# CyloRen-v_6_0.net
KiCad netlist of a schematic drawn in EAGLE
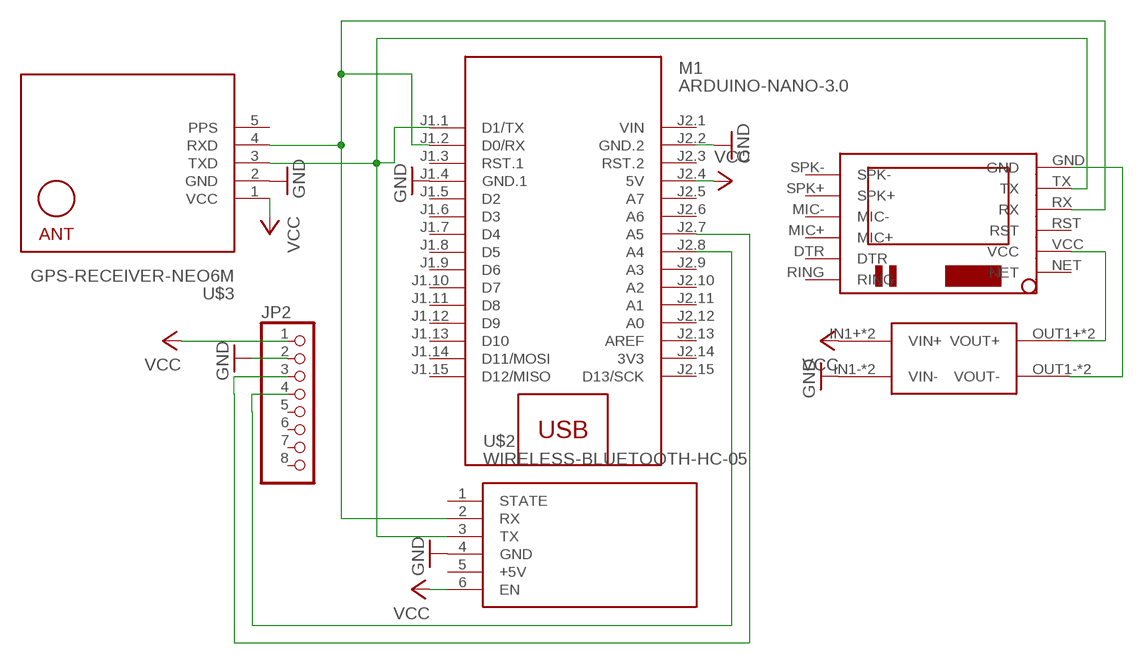
[diagram p0: schematic, sheet 1]

(export (version "E")
  (design (tool "Eeschema 10.0.6"))
  (components
    (comp (ref "JP2")
      (value "PINHD-1X8BIG")
      (footprint "eagle-import:1X08-BIG")
      (libsource (lib "eagle-import") (part "PINHD-1X8BIG"))
    )
    (comp (ref "M1")
      (value "ARDUINO-NANO-3.0")
      (footprint "eagle-import:ARDUINO-NANO-3.0")
      (libsource (lib "eagle-import") (part "ARDUINO-NANO-3.0"))
    )
    (comp (ref "U$1")
      (value "MP1584")
      (footprint "eagle-import:DC-BRICK")
      (libsource (lib "eagle-import") (part "MP1584"))
    )
    (comp (ref "U$2")
      (value "WIRELESS-BLUETOOTH-HC-05")
      (footprint "eagle-import:WIRELESS-BLUETOOTH-HC-05")
      (libsource (lib "eagle-import") (part "WIRELESS-BLUETOOTH-HC-05"))
    )
    (comp (ref "U$3")
      (value "GPS-RECEIVER-NEO6M")
      (footprint "eagle-import:GPS-RECEIVER-NEO6M")
      (libsource (lib "eagle-import") (part "GPS-RECEIVER-NEO6M"))
    )
    (comp (ref "U$4")
      (value "SIM800LMODULE")
      (footprint "eagle-import:SIM800LMODULE")
      (libsource (lib "eagle-import") (part "SIM800LMODULE"))
    )
  )
  (nets
    (net (code "1") (name "/+5V") (class "Default")
      (node (ref "U$2") (pin "5") (pinfunction "+5V_5") (pintype "power_in"))
    )
    (net (code "2") (name "/3V3") (class "Default")
      (node (ref "M1") (pin "J2.14") (pinfunction "3V3_J2.14") (pintype "power_in"))
    )
    (net (code "3") (name "/PPS") (class "Default")
      (node (ref "U$3") (pin "5") (pinfunction "PPS_5") (pintype "power_in"))
    )
    (net (code "4") (name "/VIN") (class "Default")
      (node (ref "M1") (pin "J2.1") (pinfunction "VIN_J2.1") (pintype "power_in"))
    )
    (net (code "5") (name "GND") (class "Default")
      (node (ref "JP2") (pin "2") (pinfunction "2_2") (pintype "passive"))
      (node (ref "M1") (pin "J1.4") (pinfunction "GND.1_J1.4") (pintype "power_in"))
      (node (ref "M1") (pin "J2.2") (pinfunction "GND.2_J2.2") (pintype "power_in"))
      (node (ref "U$1") (pin "IN1-") (pinfunction "VIN-_IN1-") (pintype "input"))
      (node (ref "U$1") (pin "IN2-") (pinfunction "VIN-_IN2-") (pintype "input"))
      (node (ref "U$2") (pin "4") (pinfunction "GND_4") (pintype "power_in"))
      (node (ref "U$3") (pin "2") (pinfunction "GND_2") (pintype "bidirectional"))
    )
    (net (code "6") (name "Net-(M1-A4)") (class "Default")
      (node (ref "JP2") (pin "4") (pinfunction "4_4") (pintype "passive"))
      (node (ref "M1") (pin "J2.8") (pinfunction "A4_J2.8") (pintype "bidirectional"))
    )
    (net (code "7") (name "Net-(M1-A5)") (class "Default")
      (node (ref "JP2") (pin "3") (pinfunction "3_3") (pintype "passive"))
      (node (ref "M1") (pin "J2.7") (pinfunction "A5_J2.7") (pintype "bidirectional"))
    )
    (net (code "8") (name "Net-(M1-D0{slash}RX)") (class "Default")
      (node (ref "M1") (pin "J1.2") (pinfunction "D0/RX_J1.2") (pintype "bidirectional"))
      (node (ref "U$2") (pin "2") (pinfunction "RX_2") (pintype "bidirectional"))
      (node (ref "U$3") (pin "4") (pinfunction "RXD_4") (pintype "power_in"))
      (node (ref "U$4") (pin "RX") (pinfunction "RX_RX") (pintype "bidirectional"))
    )
    (net (code "9") (name "Net-(M1-D1{slash}TX)") (class "Default")
      (node (ref "M1") (pin "J1.1") (pinfunction "D1/TX_J1.1") (pintype "bidirectional"))
      (node (ref "U$2") (pin "3") (pinfunction "TX_3") (pintype "bidirectional"))
      (node (ref "U$3") (pin "3") (pinfunction "TXD_3") (pintype "bidirectional"))
      (node (ref "U$4") (pin "TX") (pinfunction "TX_TX") (pintype "bidirectional"))
    )
    (net (code "10") (name "Net-(U$1-VOUT+-PadOUT1+)") (class "Default")
      (node (ref "U$1") (pin "OUT1+") (pinfunction "VOUT+_OUT1+") (pintype "output"))
      (node (ref "U$1") (pin "OUT2+") (pinfunction "VOUT+_OUT2+") (pintype "output"))
      (node (ref "U$4") (pin "VCC") (pinfunction "VCC_VCC") (pintype "bidirectional"))
    )
    (net (code "11") (name "Net-(U$1-VOUT--PadOUT1-)") (class "Default")
      (node (ref "U$1") (pin "OUT1-") (pinfunction "VOUT-_OUT1-") (pintype "output"))
      (node (ref "U$1") (pin "OUT2-") (pinfunction "VOUT-_OUT2-") (pintype "output"))
      (node (ref "U$4") (pin "GND") (pinfunction "GND_GND") (pintype "bidirectional"))
    )
    (net (code "12") (name "VCC") (class "Default")
      (node (ref "JP2") (pin "1") (pinfunction "1_1") (pintype "passive"))
      (node (ref "M1") (pin "J2.4") (pinfunction "5V_J2.4") (pintype "power_in"))
      (node (ref "U$1") (pin "IN1+") (pinfunction "VIN+_IN1+") (pintype "input"))
      (node (ref "U$1") (pin "IN2+") (pinfunction "VIN+_IN2+") (pintype "input"))
      (node (ref "U$2") (pin "6") (pinfunction "EN_6") (pintype "bidirectional"))
      (node (ref "U$3") (pin "1") (pinfunction "VCC_1") (pintype "bidirectional"))
    )
    (net (code "13") (name "unconnected-(JP2-Pad5)") (class "Default")
      (node (ref "JP2") (pin "5") (pinfunction "5_5") (pintype "passive"))
    )
    (net (code "14") (name "unconnected-(JP2-Pad6)") (class "Default")
      (node (ref "JP2") (pin "6") (pinfunction "6_6") (pintype "passive"))
    )
    (net (code "15") (name "unconnected-(JP2-Pad7)") (class "Default")
      (node (ref "JP2") (pin "7") (pinfunction "7_7") (pintype "passive"))
    )
    (net (code "16") (name "unconnected-(JP2-Pad8)") (class "Default")
      (node (ref "JP2") (pin "8") (pinfunction "8_8") (pintype "passive"))
    )
    (net (code "17") (name "unconnected-(M1-A0-PadJ2.12)") (class "Default")
      (node (ref "M1") (pin "J2.12") (pinfunction "A0_J2.12") (pintype "bidirectional"))
    )
    (net (code "18") (name "unconnected-(M1-A1-PadJ2.11)") (class "Default")
      (node (ref "M1") (pin "J2.11") (pinfunction "A1_J2.11") (pintype "bidirectional"))
    )
    (net (code "19") (name "unconnected-(M1-A2-PadJ2.10)") (class "Default")
      (node (ref "M1") (pin "J2.10") (pinfunction "A2_J2.10") (pintype "bidirectional"))
    )
    (net (code "20") (name "unconnected-(M1-A3-PadJ2.9)") (class "Default")
      (node (ref "M1") (pin "J2.9") (pinfunction "A3_J2.9") (pintype "bidirectional"))
    )
    (net (code "21") (name "unconnected-(M1-A6-PadJ2.6)") (class "Default")
      (node (ref "M1") (pin "J2.6") (pinfunction "A6_J2.6") (pintype "bidirectional"))
    )
    (net (code "22") (name "unconnected-(M1-A7-PadJ2.5)") (class "Default")
      (node (ref "M1") (pin "J2.5") (pinfunction "A7_J2.5") (pintype "bidirectional"))
    )
    (net (code "23") (name "unconnected-(M1-AREF-PadJ2.13)") (class "Default")
      (node (ref "M1") (pin "J2.13") (pinfunction "AREF_J2.13") (pintype "bidirectional"))
    )
    (net (code "24") (name "unconnected-(M1-D2-PadJ1.5)") (class "Default")
      (node (ref "M1") (pin "J1.5") (pinfunction "D2_J1.5") (pintype "bidirectional"))
    )
    (net (code "25") (name "unconnected-(M1-D3-PadJ1.6)") (class "Default")
      (node (ref "M1") (pin "J1.6") (pinfunction "D3_J1.6") (pintype "bidirectional"))
    )
    (net (code "26") (name "unconnected-(M1-D4-PadJ1.7)") (class "Default")
      (node (ref "M1") (pin "J1.7") (pinfunction "D4_J1.7") (pintype "bidirectional"))
    )
    (net (code "27") (name "unconnected-(M1-D5-PadJ1.8)") (class "Default")
      (node (ref "M1") (pin "J1.8") (pinfunction "D5_J1.8") (pintype "bidirectional"))
    )
    (net (code "28") (name "unconnected-(M1-D6-PadJ1.9)") (class "Default")
      (node (ref "M1") (pin "J1.9") (pinfunction "D6_J1.9") (pintype "bidirectional"))
    )
    (net (code "29") (name "unconnected-(M1-D7-PadJ1.10)") (class "Default")
      (node (ref "M1") (pin "J1.10") (pinfunction "D7_J1.10") (pintype "bidirectional"))
    )
    (net (code "30") (name "unconnected-(M1-D8-PadJ1.11)") (class "Default")
      (node (ref "M1") (pin "J1.11") (pinfunction "D8_J1.11") (pintype "bidirectional"))
    )
    (net (code "31") (name "unconnected-(M1-D9-PadJ1.12)") (class "Default")
      (node (ref "M1") (pin "J1.12") (pinfunction "D9_J1.12") (pintype "bidirectional"))
    )
    (net (code "32") (name "unconnected-(M1-D10-PadJ1.13)") (class "Default")
      (node (ref "M1") (pin "J1.13") (pinfunction "D10_J1.13") (pintype "bidirectional"))
    )
    (net (code "33") (name "unconnected-(M1-D11{slash}MOSI-PadJ1.14)") (class "Default")
      (node (ref "M1") (pin "J1.14") (pinfunction "D11/MOSI_J1.14") (pintype "bidirectional"))
    )
    (net (code "34") (name "unconnected-(M1-D12{slash}MISO-PadJ1.15)") (class "Default")
      (node (ref "M1") (pin "J1.15") (pinfunction "D12/MISO_J1.15") (pintype "bidirectional"))
    )
    (net (code "35") (name "unconnected-(M1-D13{slash}SCK-PadJ2.15)") (class "Default")
      (node (ref "M1") (pin "J2.15") (pinfunction "D13/SCK_J2.15") (pintype "bidirectional"))
    )
    (net (code "36") (name "unconnected-(M1-RST.1-PadJ1.3)") (class "Default")
      (node (ref "M1") (pin "J1.3") (pinfunction "RST.1_J1.3") (pintype "bidirectional"))
    )
    (net (code "37") (name "unconnected-(M1-RST.2-PadJ2.3)") (class "Default")
      (node (ref "M1") (pin "J2.3") (pinfunction "RST.2_J2.3") (pintype "bidirectional"))
    )
    (net (code "38") (name "unconnected-(U$2-STATE-Pad1)") (class "Default")
      (node (ref "U$2") (pin "1") (pinfunction "STATE_1") (pintype "bidirectional"))
    )
    (net (code "39") (name "unconnected-(U$4-PadDTR)") (class "Default")
      (node (ref "U$4") (pin "DTR") (pinfunction "DTR_DTR") (pintype "bidirectional"))
    )
    (net (code "40") (name "unconnected-(U$4-PadMIC+)") (class "Default")
      (node (ref "U$4") (pin "MIC+") (pinfunction "MIC+_MIC+") (pintype "bidirectional"))
    )
    (net (code "41") (name "unconnected-(U$4-PadMIC-)") (class "Default")
      (node (ref "U$4") (pin "MIC-") (pinfunction "MIC-_MIC-") (pintype "bidirectional"))
    )
    (net (code "42") (name "unconnected-(U$4-PadNET)") (class "Default")
      (node (ref "U$4") (pin "NET") (pinfunction "NET_NET") (pintype "bidirectional"))
    )
    (net (code "43") (name "unconnected-(U$4-PadRING)") (class "Default")
      (node (ref "U$4") (pin "RING") (pinfunction "RING_RING") (pintype "bidirectional"))
    )
    (net (code "44") (name "unconnected-(U$4-PadRST)") (class "Default")
      (node (ref "U$4") (pin "RST") (pinfunction "RST_RST") (pintype "bidirectional"))
    )
    (net (code "45") (name "unconnected-(U$4-PadSPK+)") (class "Default")
      (node (ref "U$4") (pin "SPK+") (pinfunction "SPK+_SPK+") (pintype "bidirectional"))
    )
    (net (code "46") (name "unconnected-(U$4-PadSPK-)") (class "Default")
      (node (ref "U$4") (pin "SPK-") (pinfunction "SPK-_SPK-") (pintype "bidirectional"))
    )
  )
)
